# Parallel_Capacitor.net
KiCad netlist of a schematic drawn in Altium Designer
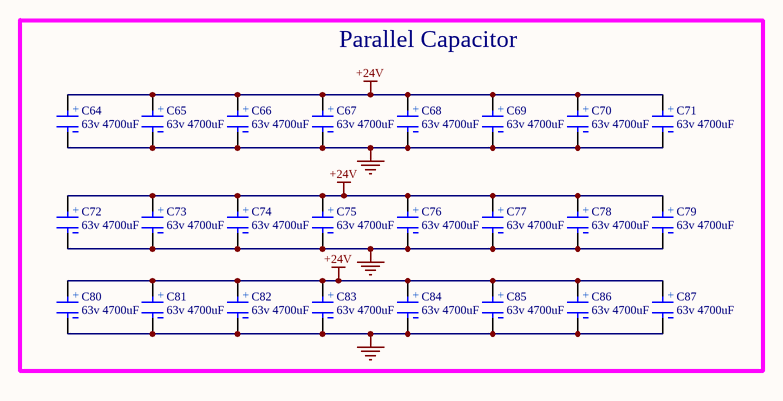
[diagram p0: Parallel_Capacitor.SchDoc]

(export (version "E")
  (design (tool "Eeschema 10.0.6"))
  (components
    (comp (ref "C64")
      (value "63v 4700uF")
      (footprint "cap 10*20")
      (description "PKL5-063V472MM450 Aluminum Electrolytic Capacitors - Snap In 63volts 4700uF 20%")
      (fields
        (field (name "MANUFACTURER") "Nichicon")
        (field (name "MANUFACTURER PART NUMBER") "LKS1J472MESZ")
      )
      (libsource (lib "LFI Power BoardSchlib1") (part "capacitor 10*20"))
    )
    (comp (ref "C65")
      (value "63v 4700uF")
      (footprint "cap 10*20")
      (description "PKL5-063V472MM450 Aluminum Electrolytic Capacitors - Snap In 63volts 4700uF 20%")
      (fields
        (field (name "MANUFACTURER") "Nichicon")
        (field (name "MANUFACTURER PART NUMBER") "LKS1J472MESZ")
      )
      (libsource (lib "LFI Power BoardSchlib1") (part "capacitor 10*20"))
    )
    (comp (ref "C66")
      (value "63v 4700uF")
      (footprint "cap 10*20")
      (description "PKL5-063V472MM450 Aluminum Electrolytic Capacitors - Snap In 63volts 4700uF 20%")
      (fields
        (field (name "MANUFACTURER") "Nichicon")
        (field (name "MANUFACTURER PART NUMBER") "LKS1J472MESZ")
      )
      (libsource (lib "LFI Power BoardSchlib1") (part "capacitor 10*20"))
    )
    (comp (ref "C67")
      (value "63v 4700uF")
      (footprint "cap 10*20")
      (description "PKL5-063V472MM450 Aluminum Electrolytic Capacitors - Snap In 63volts 4700uF 20%")
      (fields
        (field (name "MANUFACTURER") "Nichicon")
        (field (name "MANUFACTURER PART NUMBER") "LKS1J472MESZ")
      )
      (libsource (lib "LFI Power BoardSchlib1") (part "capacitor 10*20"))
    )
    (comp (ref "C68")
      (value "63v 4700uF")
      (footprint "cap 10*20")
      (description "PKL5-063V472MM450 Aluminum Electrolytic Capacitors - Snap In 63volts 4700uF 20%")
      (fields
        (field (name "MANUFACTURER") "Nichicon")
        (field (name "MANUFACTURER PART NUMBER") "LKS1J472MESZ")
      )
      (libsource (lib "LFI Power BoardSchlib1") (part "capacitor 10*20"))
    )
    (comp (ref "C69")
      (value "63v 4700uF")
      (footprint "cap 10*20")
      (description "PKL5-063V472MM450 Aluminum Electrolytic Capacitors - Snap In 63volts 4700uF 20%")
      (fields
        (field (name "MANUFACTURER") "Nichicon")
        (field (name "MANUFACTURER PART NUMBER") "LKS1J472MESZ")
      )
      (libsource (lib "LFI Power BoardSchlib1") (part "capacitor 10*20"))
    )
    (comp (ref "C70")
      (value "63v 4700uF")
      (footprint "cap 10*20")
      (description "PKL5-063V472MM450 Aluminum Electrolytic Capacitors - Snap In 63volts 4700uF 20%")
      (fields
        (field (name "MANUFACTURER") "Nichicon")
        (field (name "MANUFACTURER PART NUMBER") "LKS1J472MESZ")
      )
      (libsource (lib "LFI Power BoardSchlib1") (part "capacitor 10*20"))
    )
    (comp (ref "C71")
      (value "63v 4700uF")
      (footprint "cap 10*20")
      (description "PKL5-063V472MM450 Aluminum Electrolytic Capacitors - Snap In 63volts 4700uF 20%")
      (fields
        (field (name "MANUFACTURER") "Nichicon")
        (field (name "MANUFACTURER PART NUMBER") "LKS1J472MESZ")
      )
      (libsource (lib "LFI Power BoardSchlib1") (part "capacitor 10*20"))
    )
    (comp (ref "C72")
      (value "63v 4700uF")
      (footprint "cap 10*20")
      (description "PKL5-063V472MM450 Aluminum Electrolytic Capacitors - Snap In 63volts 4700uF 20%")
      (fields
        (field (name "MANUFACTURER") "Nichicon")
        (field (name "MANUFACTURER PART NUMBER") "LKS1J472MESZ")
      )
      (libsource (lib "LFI Power BoardSchlib1") (part "capacitor 10*20"))
    )
    (comp (ref "C73")
      (value "63v 4700uF")
      (footprint "cap 10*20")
      (description "PKL5-063V472MM450 Aluminum Electrolytic Capacitors - Snap In 63volts 4700uF 20%")
      (fields
        (field (name "MANUFACTURER") "Nichicon")
        (field (name "MANUFACTURER PART NUMBER") "LKS1J472MESZ")
      )
      (libsource (lib "LFI Power BoardSchlib1") (part "capacitor 10*20"))
    )
    (comp (ref "C74")
      (value "63v 4700uF")
      (footprint "cap 10*20")
      (description "PKL5-063V472MM450 Aluminum Electrolytic Capacitors - Snap In 63volts 4700uF 20%")
      (fields
        (field (name "MANUFACTURER") "Nichicon")
        (field (name "MANUFACTURER PART NUMBER") "LKS1J472MESZ")
      )
      (libsource (lib "LFI Power BoardSchlib1") (part "capacitor 10*20"))
    )
    (comp (ref "C75")
      (value "63v 4700uF")
      (footprint "cap 10*20")
      (description "PKL5-063V472MM450 Aluminum Electrolytic Capacitors - Snap In 63volts 4700uF 20%")
      (fields
        (field (name "MANUFACTURER") "Nichicon")
        (field (name "MANUFACTURER PART NUMBER") "LKS1J472MESZ")
      )
      (libsource (lib "LFI Power BoardSchlib1") (part "capacitor 10*20"))
    )
    (comp (ref "C76")
      (value "63v 4700uF")
      (footprint "cap 10*20")
      (description "PKL5-063V472MM450 Aluminum Electrolytic Capacitors - Snap In 63volts 4700uF 20%")
      (fields
        (field (name "MANUFACTURER") "Nichicon")
        (field (name "MANUFACTURER PART NUMBER") "LKS1J472MESZ")
      )
      (libsource (lib "LFI Power BoardSchlib1") (part "capacitor 10*20"))
    )
    (comp (ref "C77")
      (value "63v 4700uF")
      (footprint "cap 10*20")
      (description "PKL5-063V472MM450 Aluminum Electrolytic Capacitors - Snap In 63volts 4700uF 20%")
      (fields
        (field (name "MANUFACTURER") "Nichicon")
        (field (name "MANUFACTURER PART NUMBER") "LKS1J472MESZ")
      )
      (libsource (lib "LFI Power BoardSchlib1") (part "capacitor 10*20"))
    )
    (comp (ref "C78")
      (value "63v 4700uF")
      (footprint "cap 10*20")
      (description "PKL5-063V472MM450 Aluminum Electrolytic Capacitors - Snap In 63volts 4700uF 20%")
      (fields
        (field (name "MANUFACTURER") "Nichicon")
        (field (name "MANUFACTURER PART NUMBER") "LKS1J472MESZ")
      )
      (libsource (lib "LFI Power BoardSchlib1") (part "capacitor 10*20"))
    )
    (comp (ref "C79")
      (value "63v 4700uF")
      (footprint "cap 10*20")
      (description "PKL5-063V472MM450 Aluminum Electrolytic Capacitors - Snap In 63volts 4700uF 20%")
      (fields
        (field (name "MANUFACTURER") "Nichicon")
        (field (name "MANUFACTURER PART NUMBER") "LKS1J472MESZ")
      )
      (libsource (lib "LFI Power BoardSchlib1") (part "capacitor 10*20"))
    )
    (comp (ref "C80")
      (value "63v 4700uF")
      (footprint "cap 10*20")
      (description "PKL5-063V472MM450 Aluminum Electrolytic Capacitors - Snap In 63volts 4700uF 20%")
      (fields
        (field (name "MANUFACTURER") "Nichicon")
        (field (name "MANUFACTURER PART NUMBER") "LKS1J472MESZ")
      )
      (libsource (lib "LFI Power BoardSchlib1") (part "capacitor 10*20"))
    )
    (comp (ref "C81")
      (value "63v 4700uF")
      (footprint "cap 10*20")
      (description "PKL5-063V472MM450 Aluminum Electrolytic Capacitors - Snap In 63volts 4700uF 20%")
      (fields
        (field (name "MANUFACTURER") "Nichicon")
        (field (name "MANUFACTURER PART NUMBER") "LKS1J472MESZ")
      )
      (libsource (lib "LFI Power BoardSchlib1") (part "capacitor 10*20"))
    )
    (comp (ref "C82")
      (value "63v 4700uF")
      (footprint "cap 10*20")
      (description "PKL5-063V472MM450 Aluminum Electrolytic Capacitors - Snap In 63volts 4700uF 20%")
      (fields
        (field (name "MANUFACTURER") "Nichicon")
        (field (name "MANUFACTURER PART NUMBER") "LKS1J472MESZ")
      )
      (libsource (lib "LFI Power BoardSchlib1") (part "capacitor 10*20"))
    )
    (comp (ref "C83")
      (value "63v 4700uF")
      (footprint "cap 10*20")
      (description "PKL5-063V472MM450 Aluminum Electrolytic Capacitors - Snap In 63volts 4700uF 20%")
      (fields
        (field (name "MANUFACTURER") "Nichicon")
        (field (name "MANUFACTURER PART NUMBER") "LKS1J472MESZ")
      )
      (libsource (lib "LFI Power BoardSchlib1") (part "capacitor 10*20"))
    )
    (comp (ref "C84")
      (value "63v 4700uF")
      (footprint "cap 10*20")
      (description "PKL5-063V472MM450 Aluminum Electrolytic Capacitors - Snap In 63volts 4700uF 20%")
      (fields
        (field (name "MANUFACTURER") "Nichicon")
        (field (name "MANUFACTURER PART NUMBER") "LKS1J472MESZ")
      )
      (libsource (lib "LFI Power BoardSchlib1") (part "capacitor 10*20"))
    )
    (comp (ref "C85")
      (value "63v 4700uF")
      (footprint "cap 10*20")
      (description "PKL5-063V472MM450 Aluminum Electrolytic Capacitors - Snap In 63volts 4700uF 20%")
      (fields
        (field (name "MANUFACTURER") "Nichicon")
        (field (name "MANUFACTURER PART NUMBER") "LKS1J472MESZ")
      )
      (libsource (lib "LFI Power BoardSchlib1") (part "capacitor 10*20"))
    )
    (comp (ref "C86")
      (value "63v 4700uF")
      (footprint "cap 10*20")
      (description "PKL5-063V472MM450 Aluminum Electrolytic Capacitors - Snap In 63volts 4700uF 20%")
      (fields
        (field (name "MANUFACTURER") "Nichicon")
        (field (name "MANUFACTURER PART NUMBER") "LKS1J472MESZ")
      )
      (libsource (lib "LFI Power BoardSchlib1") (part "capacitor 10*20"))
    )
    (comp (ref "C87")
      (value "63v 4700uF")
      (footprint "cap 10*20")
      (description "PKL5-063V472MM450 Aluminum Electrolytic Capacitors - Snap In 63volts 4700uF 20%")
      (fields
        (field (name "MANUFACTURER") "Nichicon")
        (field (name "MANUFACTURER PART NUMBER") "LKS1J472MESZ")
      )
      (libsource (lib "LFI Power BoardSchlib1") (part "capacitor 10*20"))
    )
  )
  (nets
    (net (code "1") (name "+24V") (class "Default")
      (node (ref "C64") (pin "1") (pinfunction "1_1") (pintype "passive"))
      (node (ref "C65") (pin "1") (pinfunction "1_1") (pintype "passive"))
      (node (ref "C66") (pin "1") (pinfunction "1_1") (pintype "passive"))
      (node (ref "C67") (pin "1") (pinfunction "1_1") (pintype "passive"))
      (node (ref "C68") (pin "1") (pinfunction "1_1") (pintype "passive"))
      (node (ref "C69") (pin "1") (pinfunction "1_1") (pintype "passive"))
      (node (ref "C70") (pin "1") (pinfunction "1_1") (pintype "passive"))
      (node (ref "C71") (pin "1") (pinfunction "1_1") (pintype "passive"))
      (node (ref "C72") (pin "1") (pinfunction "1_1") (pintype "passive"))
      (node (ref "C73") (pin "1") (pinfunction "1_1") (pintype "passive"))
      (node (ref "C74") (pin "1") (pinfunction "1_1") (pintype "passive"))
      (node (ref "C75") (pin "1") (pinfunction "1_1") (pintype "passive"))
      (node (ref "C76") (pin "1") (pinfunction "1_1") (pintype "passive"))
      (node (ref "C77") (pin "1") (pinfunction "1_1") (pintype "passive"))
      (node (ref "C78") (pin "1") (pinfunction "1_1") (pintype "passive"))
      (node (ref "C79") (pin "1") (pinfunction "1_1") (pintype "passive"))
      (node (ref "C80") (pin "1") (pinfunction "1_1") (pintype "passive"))
      (node (ref "C81") (pin "1") (pinfunction "1_1") (pintype "passive"))
      (node (ref "C82") (pin "1") (pinfunction "1_1") (pintype "passive"))
      (node (ref "C83") (pin "1") (pinfunction "1_1") (pintype "passive"))
      (node (ref "C84") (pin "1") (pinfunction "1_1") (pintype "passive"))
      (node (ref "C85") (pin "1") (pinfunction "1_1") (pintype "passive"))
      (node (ref "C86") (pin "1") (pinfunction "1_1") (pintype "passive"))
      (node (ref "C87") (pin "1") (pinfunction "1_1") (pintype "passive"))
    )
    (net (code "2") (name "GND") (class "Default")
      (node (ref "C64") (pin "2") (pinfunction "2_2") (pintype "passive"))
      (node (ref "C65") (pin "2") (pinfunction "2_2") (pintype "passive"))
      (node (ref "C66") (pin "2") (pinfunction "2_2") (pintype "passive"))
      (node (ref "C67") (pin "2") (pinfunction "2_2") (pintype "passive"))
      (node (ref "C68") (pin "2") (pinfunction "2_2") (pintype "passive"))
      (node (ref "C69") (pin "2") (pinfunction "2_2") (pintype "passive"))
      (node (ref "C70") (pin "2") (pinfunction "2_2") (pintype "passive"))
      (node (ref "C71") (pin "2") (pinfunction "2_2") (pintype "passive"))
      (node (ref "C72") (pin "2") (pinfunction "2_2") (pintype "passive"))
      (node (ref "C73") (pin "2") (pinfunction "2_2") (pintype "passive"))
      (node (ref "C74") (pin "2") (pinfunction "2_2") (pintype "passive"))
      (node (ref "C75") (pin "2") (pinfunction "2_2") (pintype "passive"))
      (node (ref "C76") (pin "2") (pinfunction "2_2") (pintype "passive"))
      (node (ref "C77") (pin "2") (pinfunction "2_2") (pintype "passive"))
      (node (ref "C78") (pin "2") (pinfunction "2_2") (pintype "passive"))
      (node (ref "C79") (pin "2") (pinfunction "2_2") (pintype "passive"))
      (node (ref "C80") (pin "2") (pinfunction "2_2") (pintype "passive"))
      (node (ref "C81") (pin "2") (pinfunction "2_2") (pintype "passive"))
      (node (ref "C82") (pin "2") (pinfunction "2_2") (pintype "passive"))
      (node (ref "C83") (pin "2") (pinfunction "2_2") (pintype "passive"))
      (node (ref "C84") (pin "2") (pinfunction "2_2") (pintype "passive"))
      (node (ref "C85") (pin "2") (pinfunction "2_2") (pintype "passive"))
      (node (ref "C86") (pin "2") (pinfunction "2_2") (pintype "passive"))
      (node (ref "C87") (pin "2") (pinfunction "2_2") (pintype "passive"))
    )
  )
)
